# SSM_RGB.net
KiCad netlist of a schematic drawn in EAGLE
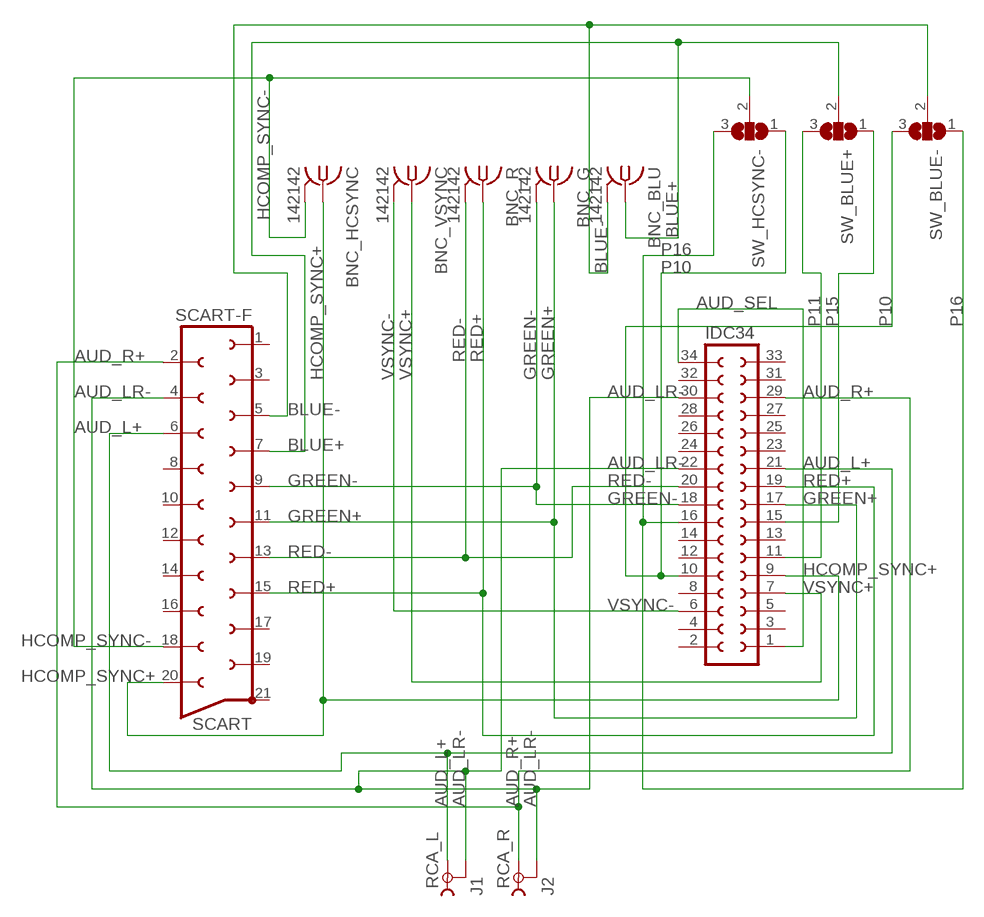
[diagram p0: schematic, sheet 1]

(export (version "E")
  (design (tool "Eeschema 10.0.6"))
  (components
    (comp (ref "BNC_BLU")
      (value "142142")
      (footprint "eagle-import:142142")
      (fields (field (name "MF") "Amphenol Connex"))
      (libsource (lib "eagle-import") (part "142142"))
    )
    (comp (ref "BNC_G")
      (value "142142")
      (footprint "eagle-import:142142")
      (fields (field (name "MF") "Amphenol Connex"))
      (libsource (lib "eagle-import") (part "142142"))
    )
    (comp (ref "BNC_HCSYNC")
      (value "142142")
      (footprint "eagle-import:142142")
      (fields (field (name "MF") "Amphenol Connex"))
      (libsource (lib "eagle-import") (part "142142"))
    )
    (comp (ref "BNC_R")
      (value "142142")
      (footprint "eagle-import:142142")
      (fields (field (name "MF") "Amphenol Connex"))
      (libsource (lib "eagle-import") (part "142142"))
    )
    (comp (ref "BNC_VSYNC")
      (value "142142")
      (footprint "eagle-import:142142")
      (fields (field (name "MF") "Amphenol Connex"))
      (libsource (lib "eagle-import") (part "142142"))
    )
    (comp (ref "IDC34")
      (value "SOCKET-34RA")
      (footprint "eagle-import:S34RA")
      (libsource (lib "eagle-import") (part "SOCKET-34RA"))
    )
    (comp (ref "RCA_L")
      (value "J1")
      (footprint "eagle-import:TOBU3")
      (fields (field (name "MF") "FARNELL") (field (name "MPN") "TOBU 3"))
      (libsource (lib "eagle-import") (part "TOBU3"))
    )
    (comp (ref "RCA_R")
      (value "J2")
      (footprint "eagle-import:TOBU3")
      (fields (field (name "MF") "FARNELL") (field (name "MPN") "TOBU 3"))
      (libsource (lib "eagle-import") (part "TOBU3"))
    )
    (comp (ref "SCART")
      (value "SCART-F")
      (footprint "eagle-import:SCART-F")
      (libsource (lib "eagle-import") (part "SCART-F"))
    )
    (comp (ref "SW_BLUE+")
      (value "SJ2W")
      (footprint "eagle-import:SJ_2")
      (libsource (lib "eagle-import") (part "SJ2W"))
    )
    (comp (ref "SW_BLUE-")
      (value "SJ2W")
      (footprint "eagle-import:SJ_2")
      (libsource (lib "eagle-import") (part "SJ2W"))
    )
    (comp (ref "SW_HCSYNC-")
      (value "SJ2W")
      (footprint "eagle-import:SJ_2")
      (libsource (lib "eagle-import") (part "SJ2W"))
    )
  )
  (nets
    (net (code "1") (name "/AUD_L+") (class "Default")
      (node (ref "IDC34") (pin "21") (pinfunction "21_21") (pintype "passive"))
      (node (ref "RCA_L") (pin "1") (pinfunction "1_1") (pintype "passive"))
      (node (ref "SCART") (pin "6") (pinfunction "6_6") (pintype "passive"))
    )
    (net (code "2") (name "/AUD_LR-") (class "Default")
      (node (ref "IDC34") (pin "22") (pinfunction "22_22") (pintype "passive"))
      (node (ref "IDC34") (pin "30") (pinfunction "30_30") (pintype "passive"))
      (node (ref "RCA_L") (pin "2") (pinfunction "2_2") (pintype "passive"))
      (node (ref "RCA_L") (pin "2@1") (pinfunction "2_2@1") (pintype "passive"))
      (node (ref "RCA_L") (pin "2@2") (pinfunction "2_2@2") (pintype "passive"))
      (node (ref "RCA_R") (pin "2") (pinfunction "2_2") (pintype "passive"))
      (node (ref "RCA_R") (pin "2@1") (pinfunction "2_2@1") (pintype "passive"))
      (node (ref "RCA_R") (pin "2@2") (pinfunction "2_2@2") (pintype "passive"))
      (node (ref "SCART") (pin "4") (pinfunction "4_4") (pintype "passive"))
    )
    (net (code "3") (name "/AUD_R+") (class "Default")
      (node (ref "IDC34") (pin "29") (pinfunction "29_29") (pintype "passive"))
      (node (ref "RCA_R") (pin "1") (pinfunction "1_1") (pintype "passive"))
      (node (ref "SCART") (pin "2") (pinfunction "2_2") (pintype "passive"))
    )
    (net (code "4") (name "/AUD_SEL") (class "Default")
      (node (ref "IDC34") (pin "1") (pinfunction "1_1") (pintype "passive"))
      (node (ref "IDC34") (pin "34") (pinfunction "34_34") (pintype "passive"))
    )
    (net (code "5") (name "/BLUE+") (class "Default")
      (node (ref "BNC_BLU") (pin "1") (pinfunction "1_1") (pintype "passive"))
      (node (ref "SCART") (pin "7") (pinfunction "7_7") (pintype "passive"))
      (node (ref "SW_BLUE+") (pin "2") (pinfunction "2_2") (pintype "passive"))
    )
    (net (code "6") (name "/BLUE-") (class "Default")
      (node (ref "BNC_BLU") (pin "2") (pinfunction "2_2") (pintype "passive"))
      (node (ref "BNC_BLU") (pin "3") (pinfunction "2_3") (pintype "passive"))
      (node (ref "BNC_BLU") (pin "4") (pinfunction "2_4") (pintype "passive"))
      (node (ref "BNC_BLU") (pin "5") (pinfunction "2_5") (pintype "passive"))
      (node (ref "SCART") (pin "5") (pinfunction "5_5") (pintype "passive"))
      (node (ref "SW_BLUE-") (pin "2") (pinfunction "2_2") (pintype "passive"))
    )
    (net (code "7") (name "/GREEN+") (class "Default")
      (node (ref "BNC_G") (pin "1") (pinfunction "1_1") (pintype "passive"))
      (node (ref "IDC34") (pin "17") (pinfunction "17_17") (pintype "passive"))
      (node (ref "SCART") (pin "11") (pinfunction "11_11") (pintype "passive"))
    )
    (net (code "8") (name "/GREEN-") (class "Default")
      (node (ref "BNC_G") (pin "2") (pinfunction "2_2") (pintype "passive"))
      (node (ref "BNC_G") (pin "3") (pinfunction "2_3") (pintype "passive"))
      (node (ref "BNC_G") (pin "4") (pinfunction "2_4") (pintype "passive"))
      (node (ref "BNC_G") (pin "5") (pinfunction "2_5") (pintype "passive"))
      (node (ref "IDC34") (pin "18") (pinfunction "18_18") (pintype "passive"))
      (node (ref "SCART") (pin "9") (pinfunction "9_9") (pintype "passive"))
    )
    (net (code "9") (name "/HCOMP_SYNC+") (class "Default")
      (node (ref "BNC_HCSYNC") (pin "1") (pinfunction "1_1") (pintype "passive"))
      (node (ref "IDC34") (pin "9") (pinfunction "9_9") (pintype "passive"))
      (node (ref "SCART") (pin "20") (pinfunction "20_20") (pintype "passive"))
    )
    (net (code "10") (name "/HCOMP_SYNC-") (class "Default")
      (node (ref "BNC_HCSYNC") (pin "2") (pinfunction "2_2") (pintype "passive"))
      (node (ref "BNC_HCSYNC") (pin "3") (pinfunction "2_3") (pintype "passive"))
      (node (ref "BNC_HCSYNC") (pin "4") (pinfunction "2_4") (pintype "passive"))
      (node (ref "BNC_HCSYNC") (pin "5") (pinfunction "2_5") (pintype "passive"))
      (node (ref "SCART") (pin "18") (pinfunction "18_18") (pintype "passive"))
      (node (ref "SW_HCSYNC-") (pin "2") (pinfunction "2_2") (pintype "passive"))
    )
    (net (code "11") (name "/P10") (class "Default")
      (node (ref "IDC34") (pin "10") (pinfunction "10_10") (pintype "passive"))
      (node (ref "SW_BLUE-") (pin "3") (pinfunction "3_3") (pintype "passive"))
      (node (ref "SW_HCSYNC-") (pin "1") (pinfunction "1_1") (pintype "passive"))
    )
    (net (code "12") (name "/P11") (class "Default")
      (node (ref "IDC34") (pin "11") (pinfunction "11_11") (pintype "passive"))
      (node (ref "SW_BLUE+") (pin "3") (pinfunction "3_3") (pintype "passive"))
    )
    (net (code "13") (name "/P15") (class "Default")
      (node (ref "IDC34") (pin "15") (pinfunction "15_15") (pintype "passive"))
      (node (ref "SW_BLUE+") (pin "1") (pinfunction "1_1") (pintype "passive"))
    )
    (net (code "14") (name "/P16") (class "Default")
      (node (ref "IDC34") (pin "16") (pinfunction "16_16") (pintype "passive"))
      (node (ref "SW_BLUE-") (pin "1") (pinfunction "1_1") (pintype "passive"))
      (node (ref "SW_HCSYNC-") (pin "3") (pinfunction "3_3") (pintype "passive"))
    )
    (net (code "15") (name "/RED+") (class "Default")
      (node (ref "BNC_R") (pin "1") (pinfunction "1_1") (pintype "passive"))
      (node (ref "IDC34") (pin "19") (pinfunction "19_19") (pintype "passive"))
      (node (ref "SCART") (pin "15") (pinfunction "15_15") (pintype "passive"))
    )
    (net (code "16") (name "/RED-") (class "Default")
      (node (ref "BNC_R") (pin "2") (pinfunction "2_2") (pintype "passive"))
      (node (ref "BNC_R") (pin "3") (pinfunction "2_3") (pintype "passive"))
      (node (ref "BNC_R") (pin "4") (pinfunction "2_4") (pintype "passive"))
      (node (ref "BNC_R") (pin "5") (pinfunction "2_5") (pintype "passive"))
      (node (ref "IDC34") (pin "20") (pinfunction "20_20") (pintype "passive"))
      (node (ref "SCART") (pin "13") (pinfunction "13_13") (pintype "passive"))
    )
    (net (code "17") (name "/VSYNC+") (class "Default")
      (node (ref "BNC_VSYNC") (pin "1") (pinfunction "1_1") (pintype "passive"))
      (node (ref "IDC34") (pin "7") (pinfunction "7_7") (pintype "passive"))
    )
    (net (code "18") (name "/VSYNC-") (class "Default")
      (node (ref "BNC_VSYNC") (pin "2") (pinfunction "2_2") (pintype "passive"))
      (node (ref "BNC_VSYNC") (pin "3") (pinfunction "2_3") (pintype "passive"))
      (node (ref "BNC_VSYNC") (pin "4") (pinfunction "2_4") (pintype "passive"))
      (node (ref "BNC_VSYNC") (pin "5") (pinfunction "2_5") (pintype "passive"))
      (node (ref "IDC34") (pin "6") (pinfunction "6_6") (pintype "passive"))
    )
    (net (code "19") (name "unconnected-(IDC34-Pad2)") (class "Default")
      (node (ref "IDC34") (pin "2") (pinfunction "2_2") (pintype "passive"))
    )
    (net (code "20") (name "unconnected-(IDC34-Pad3)") (class "Default")
      (node (ref "IDC34") (pin "3") (pinfunction "3_3") (pintype "passive"))
    )
    (net (code "21") (name "unconnected-(IDC34-Pad4)") (class "Default")
      (node (ref "IDC34") (pin "4") (pinfunction "4_4") (pintype "passive"))
    )
    (net (code "22") (name "unconnected-(IDC34-Pad5)") (class "Default")
      (node (ref "IDC34") (pin "5") (pinfunction "5_5") (pintype "passive"))
    )
    (net (code "23") (name "unconnected-(IDC34-Pad8)") (class "Default")
      (node (ref "IDC34") (pin "8") (pinfunction "8_8") (pintype "passive"))
    )
    (net (code "24") (name "unconnected-(IDC34-Pad12)") (class "Default")
      (node (ref "IDC34") (pin "12") (pinfunction "12_12") (pintype "passive"))
    )
    (net (code "25") (name "unconnected-(IDC34-Pad13)") (class "Default")
      (node (ref "IDC34") (pin "13") (pinfunction "13_13") (pintype "passive"))
    )
    (net (code "26") (name "unconnected-(IDC34-Pad14)") (class "Default")
      (node (ref "IDC34") (pin "14") (pinfunction "14_14") (pintype "passive"))
    )
    (net (code "27") (name "unconnected-(IDC34-Pad23)") (class "Default")
      (node (ref "IDC34") (pin "23") (pinfunction "23_23") (pintype "passive"))
    )
    (net (code "28") (name "unconnected-(IDC34-Pad24)") (class "Default")
      (node (ref "IDC34") (pin "24") (pinfunction "24_24") (pintype "passive"))
    )
    (net (code "29") (name "unconnected-(IDC34-Pad25)") (class "Default")
      (node (ref "IDC34") (pin "25") (pinfunction "25_25") (pintype "passive"))
    )
    (net (code "30") (name "unconnected-(IDC34-Pad26)") (class "Default")
      (node (ref "IDC34") (pin "26") (pinfunction "26_26") (pintype "passive"))
    )
    (net (code "31") (name "unconnected-(IDC34-Pad27)") (class "Default")
      (node (ref "IDC34") (pin "27") (pinfunction "27_27") (pintype "passive"))
    )
    (net (code "32") (name "unconnected-(IDC34-Pad28)") (class "Default")
      (node (ref "IDC34") (pin "28") (pinfunction "28_28") (pintype "passive"))
    )
    (net (code "33") (name "unconnected-(IDC34-Pad31)") (class "Default")
      (node (ref "IDC34") (pin "31") (pinfunction "31_31") (pintype "passive"))
    )
    (net (code "34") (name "unconnected-(IDC34-Pad32)") (class "Default")
      (node (ref "IDC34") (pin "32") (pinfunction "32_32") (pintype "passive"))
    )
    (net (code "35") (name "unconnected-(IDC34-Pad33)") (class "Default")
      (node (ref "IDC34") (pin "33") (pinfunction "33_33") (pintype "passive"))
    )
    (net (code "36") (name "unconnected-(SCART-Pad1)") (class "Default")
      (node (ref "SCART") (pin "1") (pinfunction "1_1") (pintype "passive"))
    )
    (net (code "37") (name "unconnected-(SCART-Pad3)") (class "Default")
      (node (ref "SCART") (pin "3") (pinfunction "3_3") (pintype "passive"))
    )
    (net (code "38") (name "unconnected-(SCART-Pad8)") (class "Default")
      (node (ref "SCART") (pin "8") (pinfunction "8_8") (pintype "passive"))
    )
    (net (code "39") (name "unconnected-(SCART-Pad10)") (class "Default")
      (node (ref "SCART") (pin "10") (pinfunction "10_10") (pintype "passive"))
    )
    (net (code "40") (name "unconnected-(SCART-Pad12)") (class "Default")
      (node (ref "SCART") (pin "12") (pinfunction "12_12") (pintype "passive"))
    )
    (net (code "41") (name "unconnected-(SCART-Pad14)") (class "Default")
      (node (ref "SCART") (pin "14") (pinfunction "14_14") (pintype "passive"))
    )
    (net (code "42") (name "unconnected-(SCART-Pad16)") (class "Default")
      (node (ref "SCART") (pin "16") (pinfunction "16_16") (pintype "passive"))
    )
    (net (code "43") (name "unconnected-(SCART-Pad17)") (class "Default")
      (node (ref "SCART") (pin "17") (pinfunction "17_17") (pintype "passive"))
    )
    (net (code "44") (name "unconnected-(SCART-Pad19)") (class "Default")
      (node (ref "SCART") (pin "19") (pinfunction "19_19") (pintype "passive"))
    )
    (net (code "45") (name "unconnected-(SCART-Pad21)") (class "Default")
      (node (ref "SCART") (pin "21") (pinfunction "21_21") (pintype "passive"))
    )
  )
)
